# SCH_EEE3088F-Sphora_2025-04-07.net
KiCad netlist of a schematic drawn in EasyEDA
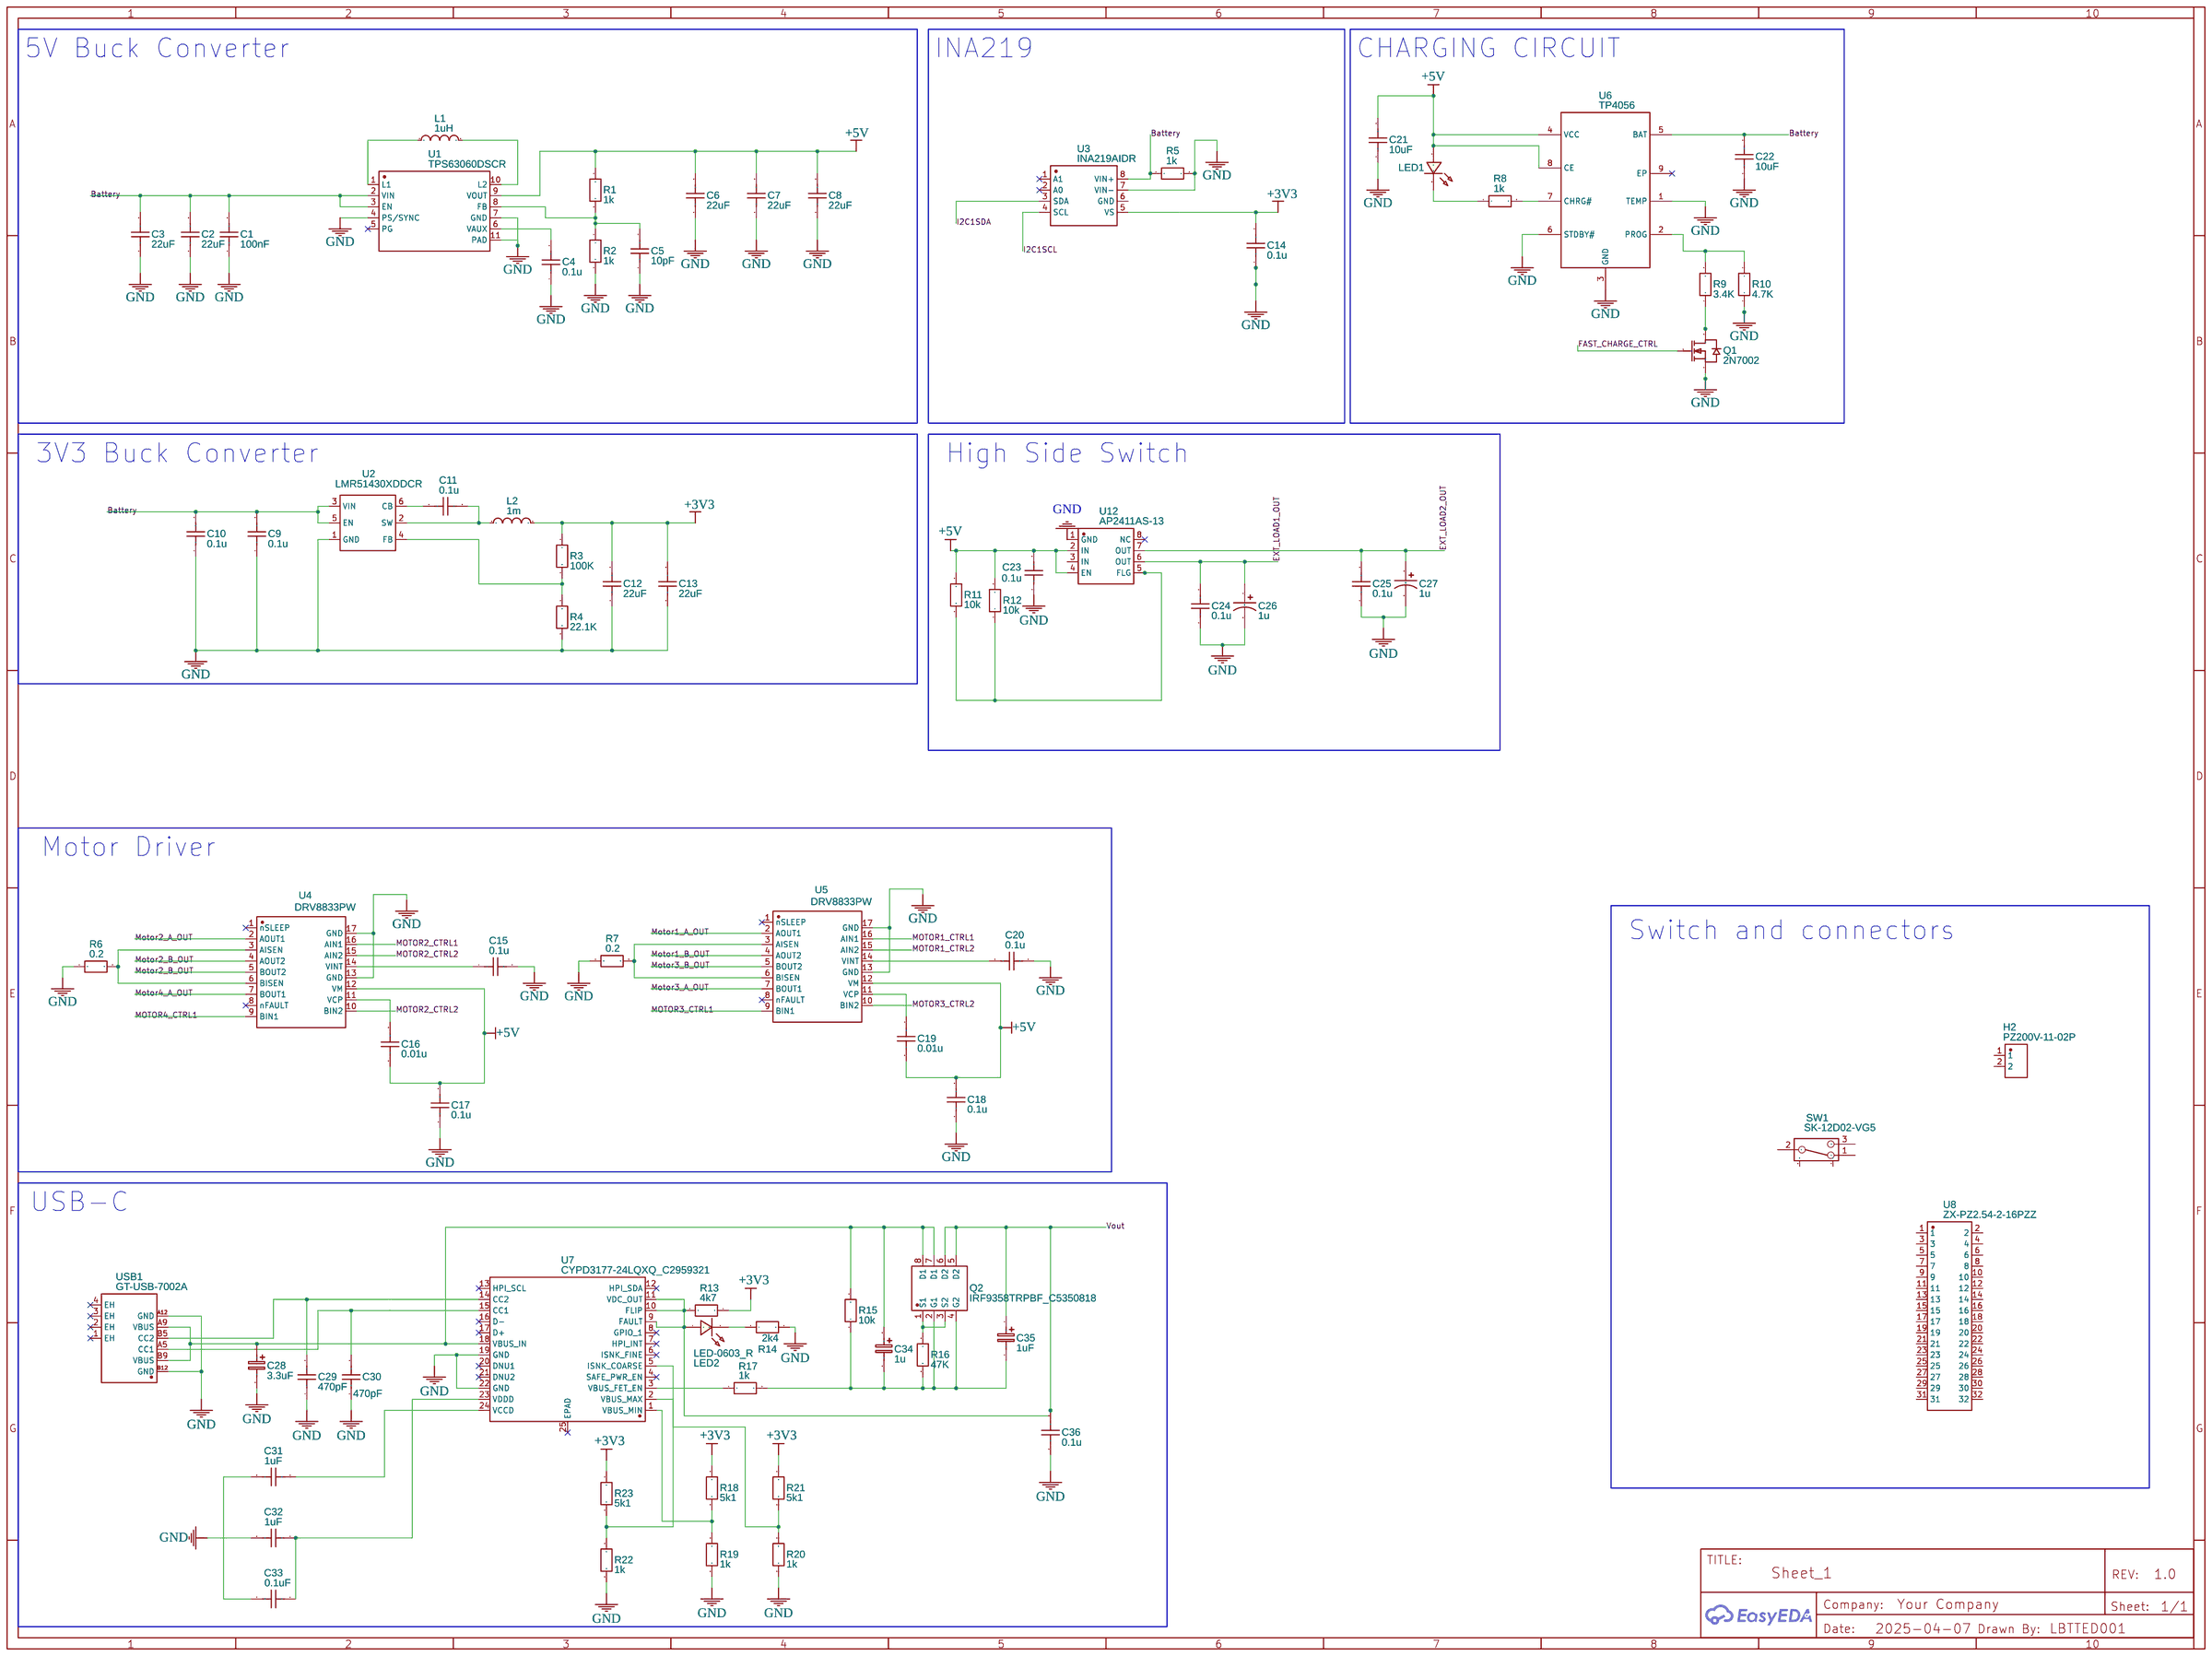
[diagram p0: schematic sheet]

(export (version "E")
  (design (tool "Eeschema 10.0.6"))
  (components
    (comp (ref "C1") (value "100nF") (libsource (lib "") (part "C_0402_US_1")))
    (comp (ref "C2") (value "22uF") (libsource (lib "") (part "C_0402_US_1")))
    (comp (ref "C3") (value "22uF") (libsource (lib "") (part "C_0402_US_1")))
    (comp (ref "C4") (value "0.1u") (libsource (lib "") (part "C_0402_US_1")))
    (comp (ref "C5") (value "10pF") (libsource (lib "") (part "C_0402_US_1")))
    (comp (ref "C6") (value "22uF") (libsource (lib "") (part "C_0402_US_1")))
    (comp (ref "C7") (value "22uF") (libsource (lib "") (part "C_0402_US_1")))
    (comp (ref "C8") (value "22uF") (libsource (lib "") (part "C_0402_US_1")))
    (comp (ref "C9") (value "0.1u") (libsource (lib "") (part "C_0402_US_1")))
    (comp (ref "C10") (value "0.1u") (libsource (lib "") (part "C_0402_US_1")))
    (comp (ref "C11") (value "0.1u") (libsource (lib "") (part "C_0402_US_2")))
    (comp (ref "C12") (value "22uF") (libsource (lib "") (part "C_0402_US_1")))
    (comp (ref "C13") (value "22uF") (libsource (lib "") (part "C_0402_US_1")))
    (comp (ref "C14") (value "0.1u") (libsource (lib "") (part "C_0402_US_3")))
    (comp (ref "C15") (value "0.1u") (libsource (lib "") (part "C_0402_US_2")))
    (comp (ref "C16") (value "0.01u") (libsource (lib "") (part "C_0402_US_1")))
    (comp (ref "C17") (value "0.1u") (libsource (lib "") (part "C_0402_US_1")))
    (comp (ref "C18") (value "0.1u") (libsource (lib "") (part "C_0402_US_1")))
    (comp (ref "C19") (value "0.01u") (libsource (lib "") (part "C_0402_US_1")))
    (comp (ref "C20") (value "0.1u") (libsource (lib "") (part "C_0402_US_2")))
    (comp (ref "C21") (value "10uF") (libsource (lib "") (part "C_0402_US_1")))
    (comp (ref "C22") (value "10uF") (libsource (lib "") (part "C_0402_US_1")))
    (comp (ref "C23") (value "0.1u") (libsource (lib "") (part "C_0402_US_1")))
    (comp (ref "C24") (value "0.1u") (libsource (lib "") (part "C_0402_US_1")))
    (comp (ref "C25") (value "0.1u") (libsource (lib "") (part "C_0402_US_1")))
    (comp (ref "C26") (value "1u") (libsource (lib "") (part "C_Tan_SMD_A_US")))
    (comp (ref "C27") (value "1u") (libsource (lib "") (part "C_Tan_SMD_A_US")))
    (comp (ref "C28") (value "3.3uF") (libsource (lib "") (part "C_Tan_SMD_A_EU_1")))
    (comp (ref "C29") (value "470pF") (libsource (lib "") (part "C_0402_US_1")))
    (comp (ref "C30") (value "470pF") (libsource (lib "") (part "C_0402_US_1")))
    (comp (ref "C31") (value "1uF") (libsource (lib "") (part "C_0402_US")))
    (comp (ref "C32") (value "1uF") (libsource (lib "") (part "C_0402_US")))
    (comp (ref "C33") (value "0.1uF") (libsource (lib "") (part "C_0402_US")))
    (comp (ref "C34") (value "1u") (libsource (lib "") (part "C_Tan_SMD_A_EU")))
    (comp (ref "C35") (value "1uF") (libsource (lib "") (part "C_Tan_SMD_A_EU")))
    (comp (ref "C36") (value "0.1u") (libsource (lib "") (part "C_0402_US_1")))
    (comp (ref "H2")
      (value "PZ200V-11-02P")
      (fields (field (name "Manufacturer") "XFCN(兴飞)"))
      (libsource (lib "") (part "PZ200V-11-02P"))
    )
    (comp (ref "L1") (value "1uH") (libsource (lib "") (part "L0603_US")))
    (comp (ref "L2") (value "1m") (libsource (lib "") (part "L0603_US")))
    (comp (ref "LED1")
      (value "LED-0603_R")
      (fields
        (field (name "Manufacturer Part") "19-217/R6C-AL1M2VY/3T")
        (field (name "Manufacturer") "EVERLIGHT(台湾亿光)")
      )
      (libsource (lib "") (part "LED-0603_R"))
    )
    (comp (ref "LED2")
      (value "LED-0603_R")
      (fields
        (field (name "Manufacturer Part") "19-217/R6C-AL1M2VY/3T")
        (field (name "Manufacturer") "EVERLIGHT(台湾亿光)")
      )
      (libsource (lib "") (part "LED-0603_R_1"))
    )
    (comp (ref "Q1")
      (value "2N7002")
      (fields (field (name "Manufacturer Part") "2N7002,215") (field (name "Manufacturer") "Nexperia"))
      (libsource (lib "") (part "2N7002"))
    )
    (comp (ref "Q2")
      (value "IRF9358TRPBF_C5350818")
      (fields
        (field (name "Manufacturer Part") "IRF9358TRPBF")
        (field (name "Manufacturer") "TECH PUBLIC(台舟)")
      )
      (libsource (lib "") (part "IRF9358TRPBF_C5350818"))
    )
    (comp (ref "R1") (value "1k") (libsource (lib "") (part "R_0402_EU")))
    (comp (ref "R2") (value "1k") (libsource (lib "") (part "R_0402_EU")))
    (comp (ref "R3") (value "100K") (libsource (lib "") (part "R_0402_EU_1")))
    (comp (ref "R4") (value "22.1K") (libsource (lib "") (part "R_0402_EU_1")))
    (comp (ref "R5") (value "1k") (libsource (lib "") (part "R_0402_EU_2")))
    (comp (ref "R6") (value "0.2") (libsource (lib "") (part "R_0402_EU_2")))
    (comp (ref "R7") (value "0.2") (libsource (lib "") (part "R_0402_EU_2")))
    (comp (ref "R8") (value "1k") (libsource (lib "") (part "R_0402_EU_2")))
    (comp (ref "R9") (value "3.4K") (libsource (lib "") (part "R_0402_EU_1")))
    (comp (ref "R10") (value "4.7K") (libsource (lib "") (part "R_0402_EU_1")))
    (comp (ref "R11") (value "10k") (libsource (lib "") (part "R_0402_EU_1")))
    (comp (ref "R12") (value "10k") (libsource (lib "") (part "R_0402_EU_1")))
    (comp (ref "R13") (value "4k7") (libsource (lib "") (part "R_0402_EU_2")))
    (comp (ref "R14") (value "2k4") (libsource (lib "") (part "R_0402_EU_2")))
    (comp (ref "R15") (value "10k") (libsource (lib "") (part "R_0402_EU_1")))
    (comp (ref "R16") (value "47K") (libsource (lib "") (part "R_0402_EU")))
    (comp (ref "R17") (value "1k") (libsource (lib "") (part "R_0402_EU_2")))
    (comp (ref "R18") (value "5k1") (libsource (lib "") (part "R_0402_EU")))
    (comp (ref "R19") (value "1k") (libsource (lib "") (part "R_0402_EU")))
    (comp (ref "R20") (value "1k") (libsource (lib "") (part "R_0402_EU")))
    (comp (ref "R21") (value "5k1") (libsource (lib "") (part "R_0402_EU")))
    (comp (ref "R22") (value "1k") (libsource (lib "") (part "R_0402_EU")))
    (comp (ref "R23") (value "5k1") (libsource (lib "") (part "R_0402_EU")))
    (comp (ref "SW1")
      (value "SK-12D02-VG5")
      (fields (field (name "Manufacturer") "Rectangular Connectors - Contacts"))
      (libsource (lib "") (part "SK-12D02-VG5"))
    )
    (comp (ref "U1")
      (value "TPS63060DSCR")
      (fields (field (name "Manufacturer") "TI(德州仪器)"))
      (libsource (lib "") (part "TPS63060DSCR"))
    )
    (comp (ref "U2")
      (value "LMR51430XDDCR")
      (fields (field (name "Manufacturer") "TI(德州仪器)"))
      (libsource (lib "") (part "LMR51430XDDCR"))
    )
    (comp (ref "U3")
      (value "INA219AIDR")
      (fields (field (name "Manufacturer") "TI(德州仪器)"))
      (libsource (lib "") (part "INA219AIDR"))
    )
    (comp (ref "U4") (value "DRV8833PW") (libsource (lib "") (part "DRV8833PW")))
    (comp (ref "U5") (value "DRV8833PW") (libsource (lib "") (part "DRV8833PW")))
    (comp (ref "U6")
      (value "TP4056")
      (fields
        (field (name "Manufacturer Part") "TP4056-42-ESOP8")
        (field (name "Manufacturer") "TOPPOWER(南京拓微)")
      )
      (libsource (lib "") (part "TP4056"))
    )
    (comp (ref "U7")
      (value "CYPD3177-24LQXQ_C2959321")
      (fields
        (field (name "Manufacturer Part") "CYPD3177-24LQXQ")
        (field (name "Manufacturer") "Infineon/CYPRESS(赛普拉斯)")
      )
      (libsource (lib "") (part "CYPD3177-24LQXQ_C2959321"))
    )
    (comp (ref "U8")
      (value "ZX-PZ2.54-2-16PZZ")
      (fields (field (name "Manufacturer") "Megastar(兆星)"))
      (libsource (lib "") (part "ZX-PZ2.54-2-16PZZ"))
    )
    (comp (ref "U12")
      (value "AP2411AS-13")
      (fields (field (name "Manufacturer") "DIODES(美台)"))
      (libsource (lib "") (part "AP2411AS-13"))
    )
    (comp (ref "USB1")
      (value "GT-USB-7002A")
      (fields (field (name "Manufacturer") "G-Switch(品赞)"))
      (libsource (lib "") (part "GT-USB-7002A"))
    )
  )
  (nets
    (net (code "1") (name "+3V3") (class "Default")
      (node (ref "C12") (pin "2") (pinfunction "2_2") (pintype "unspecified"))
      (node (ref "C13") (pin "2") (pinfunction "2_2") (pintype "unspecified"))
      (node (ref "C14") (pin "1") (pinfunction "1_1") (pintype "unspecified"))
      (node (ref "L2") (pin "2") (pinfunction "2_2") (pintype "unspecified"))
      (node (ref "R13") (pin "2") (pinfunction "2_2") (pintype "unspecified"))
      (node (ref "R18") (pin "1") (pinfunction "1_1") (pintype "unspecified"))
      (node (ref "R21") (pin "1") (pinfunction "1_1") (pintype "unspecified"))
      (node (ref "R23") (pin "1") (pinfunction "1_1") (pintype "unspecified"))
      (node (ref "R3") (pin "2") (pinfunction "2_2") (pintype "unspecified"))
      (node (ref "U3") (pin "5") (pinfunction "VS_5") (pintype "unspecified"))
    )
    (net (code "2") (name "+5V") (class "Default")
      (node (ref "C16") (pin "1") (pinfunction "1_1") (pintype "unspecified"))
      (node (ref "C17") (pin "2") (pinfunction "2_2") (pintype "unspecified"))
      (node (ref "C18") (pin "2") (pinfunction "2_2") (pintype "unspecified"))
      (node (ref "C19") (pin "1") (pinfunction "1_1") (pintype "unspecified"))
      (node (ref "C21") (pin "2") (pinfunction "2_2") (pintype "unspecified"))
      (node (ref "C23") (pin "2") (pinfunction "2_2") (pintype "unspecified"))
      (node (ref "C6") (pin "2") (pinfunction "2_2") (pintype "unspecified"))
      (node (ref "C7") (pin "2") (pinfunction "2_2") (pintype "unspecified"))
      (node (ref "C8") (pin "2") (pinfunction "2_2") (pintype "unspecified"))
      (node (ref "LED1") (pin "1") (pinfunction "1_1") (pintype "unspecified"))
      (node (ref "R1") (pin "1") (pinfunction "1_1") (pintype "unspecified"))
      (node (ref "R11") (pin "2") (pinfunction "2_2") (pintype "unspecified"))
      (node (ref "R12") (pin "2") (pinfunction "2_2") (pintype "unspecified"))
      (node (ref "U1") (pin "9") (pinfunction "VOUT_9") (pintype "unspecified"))
      (node (ref "U12") (pin "2") (pinfunction "IN_2") (pintype "unspecified"))
      (node (ref "U12") (pin "4") (pinfunction "EN_4") (pintype "unspecified"))
      (node (ref "U4") (pin "12") (pinfunction "VM_12") (pintype "unspecified"))
      (node (ref "U5") (pin "12") (pinfunction "VM_12") (pintype "unspecified"))
      (node (ref "U6") (pin "4") (pinfunction "VCC_4") (pintype "unspecified"))
      (node (ref "U6") (pin "8") (pinfunction "CE_8") (pintype "unspecified"))
    )
    (net (code "3") (name "/Battery") (class "Default")
      (node (ref "C1") (pin "2") (pinfunction "2_2") (pintype "unspecified"))
      (node (ref "C10") (pin "2") (pinfunction "2_2") (pintype "unspecified"))
      (node (ref "C2") (pin "2") (pinfunction "2_2") (pintype "unspecified"))
      (node (ref "C22") (pin "2") (pinfunction "2_2") (pintype "unspecified"))
      (node (ref "C3") (pin "2") (pinfunction "2_2") (pintype "unspecified"))
      (node (ref "C9") (pin "2") (pinfunction "2_2") (pintype "unspecified"))
      (node (ref "R5") (pin "1") (pinfunction "1_1") (pintype "unspecified"))
      (node (ref "U1") (pin "2") (pinfunction "VIN_2") (pintype "unspecified"))
      (node (ref "U1") (pin "3") (pinfunction "EN_3") (pintype "unspecified"))
      (node (ref "U2") (pin "3") (pinfunction "VIN_3") (pintype "unspecified"))
      (node (ref "U2") (pin "5") (pinfunction "EN_5") (pintype "unspecified"))
      (node (ref "U3") (pin "8") (pinfunction "VIN+_8") (pintype "unspecified"))
      (node (ref "U6") (pin "5") (pinfunction "BAT_5") (pintype "unspecified"))
    )
    (net (code "4") (name "/EXT_LOAD1_OUT") (class "Default")
      (node (ref "C24") (pin "2") (pinfunction "2_2") (pintype "unspecified"))
      (node (ref "C26") (pin "1") (pinfunction "1_1") (pintype "unspecified"))
      (node (ref "U12") (pin "6") (pinfunction "OUT_6") (pintype "unspecified"))
    )
    (net (code "5") (name "/EXT_LOAD2_OUT") (class "Default")
      (node (ref "C25") (pin "2") (pinfunction "2_2") (pintype "unspecified"))
      (node (ref "C27") (pin "1") (pinfunction "1_1") (pintype "unspecified"))
      (node (ref "U12") (pin "7") (pinfunction "OUT_7") (pintype "unspecified"))
    )
    (net (code "6") (name "/FAST_CHARGE_CTRL") (class "Default")
      (node (ref "Q1") (pin "1") (pinfunction "G_1") (pintype "unspecified"))
    )
    (net (code "7") (name "/I2C1SCL") (class "Default")
      (node (ref "U3") (pin "4") (pinfunction "SCL_4") (pintype "unspecified"))
    )
    (net (code "8") (name "/I2C1SDA") (class "Default")
      (node (ref "U3") (pin "3") (pinfunction "SDA_3") (pintype "unspecified"))
    )
    (net (code "9") (name "/MOTOR1_CTRL1") (class "Default")
      (node (ref "U5") (pin "16") (pinfunction "AIN1_16") (pintype "unspecified"))
    )
    (net (code "10") (name "/MOTOR1_CTRL2") (class "Default")
      (node (ref "U5") (pin "15") (pinfunction "AIN2_15") (pintype "unspecified"))
    )
    (net (code "11") (name "/MOTOR2_CTRL1") (class "Default")
      (node (ref "U4") (pin "16") (pinfunction "AIN1_16") (pintype "unspecified"))
    )
    (net (code "12") (name "/MOTOR2_CTRL2") (class "Default")
      (node (ref "U4") (pin "10") (pinfunction "BIN2_10") (pintype "unspecified"))
      (node (ref "U4") (pin "15") (pinfunction "AIN2_15") (pintype "unspecified"))
    )
    (net (code "13") (name "/MOTOR3_CTRL1") (class "Default")
      (node (ref "U5") (pin "9") (pinfunction "BIN1_9") (pintype "unspecified"))
    )
    (net (code "14") (name "/MOTOR3_CTRL2") (class "Default")
      (node (ref "U5") (pin "10") (pinfunction "BIN2_10") (pintype "unspecified"))
    )
    (net (code "15") (name "/MOTOR4_CTRL1") (class "Default")
      (node (ref "U4") (pin "9") (pinfunction "BIN1_9") (pintype "unspecified"))
    )
    (net (code "16") (name "/Motor1_A_OUT") (class "Default")
      (node (ref "U5") (pin "2") (pinfunction "AOUT1_2") (pintype "unspecified"))
    )
    (net (code "17") (name "/Motor1_B_OUT") (class "Default")
      (node (ref "U5") (pin "4") (pinfunction "AOUT2_4") (pintype "unspecified"))
    )
    (net (code "18") (name "/Motor2_A_OUT") (class "Default")
      (node (ref "U4") (pin "2") (pinfunction "AOUT1_2") (pintype "unspecified"))
    )
    (net (code "19") (name "/Motor2_B_OUT") (class "Default")
      (node (ref "U4") (pin "4") (pinfunction "AOUT2_4") (pintype "unspecified"))
      (node (ref "U4") (pin "5") (pinfunction "BOUT2_5") (pintype "unspecified"))
    )
    (net (code "20") (name "/Motor3_A_OUT") (class "Default")
      (node (ref "U5") (pin "7") (pinfunction "BOUT1_7") (pintype "unspecified"))
    )
    (net (code "21") (name "/Motor3_B_OUT") (class "Default")
      (node (ref "U5") (pin "5") (pinfunction "BOUT2_5") (pintype "unspecified"))
    )
    (net (code "22") (name "/Motor4_A_OUT") (class "Default")
      (node (ref "U4") (pin "7") (pinfunction "BOUT1_7") (pintype "unspecified"))
    )
    (net (code "23") (name "/Vout") (class "Default")
      (node (ref "C35") (pin "1") (pinfunction "1_1") (pintype "unspecified"))
      (node (ref "C36") (pin "2") (pinfunction "2_2") (pintype "unspecified"))
      (node (ref "LED2") (pin "1") (pinfunction "1_1") (pintype "unspecified"))
      (node (ref "Q2") (pin "5") (pinfunction "D2_5") (pintype "unspecified"))
      (node (ref "Q2") (pin "6") (pinfunction "D2_6") (pintype "unspecified"))
      (node (ref "R13") (pin "1") (pinfunction "1_1") (pintype "unspecified"))
      (node (ref "U7") (pin "10") (pinfunction "FLIP_10") (pintype "unspecified"))
      (node (ref "U7") (pin "11") (pinfunction "VDC_OUT_11") (pintype "unspecified"))
      (node (ref "U7") (pin "9") (pinfunction "FAULT_9") (pintype "unspecified"))
    )
    (net (code "24") (name "GND") (class "Default")
      (node (ref "C1") (pin "1") (pinfunction "1_1") (pintype "unspecified"))
      (node (ref "C10") (pin "1") (pinfunction "1_1") (pintype "unspecified"))
      (node (ref "C12") (pin "1") (pinfunction "1_1") (pintype "unspecified"))
      (node (ref "C13") (pin "1") (pinfunction "1_1") (pintype "unspecified"))
      (node (ref "C14") (pin "2") (pinfunction "2_2") (pintype "unspecified"))
      (node (ref "C15") (pin "2") (pinfunction "2_2") (pintype "unspecified"))
      (node (ref "C17") (pin "1") (pinfunction "1_1") (pintype "unspecified"))
      (node (ref "C18") (pin "1") (pinfunction "1_1") (pintype "unspecified"))
      (node (ref "C2") (pin "1") (pinfunction "1_1") (pintype "unspecified"))
      (node (ref "C20") (pin "2") (pinfunction "2_2") (pintype "unspecified"))
      (node (ref "C21") (pin "1") (pinfunction "1_1") (pintype "unspecified"))
      (node (ref "C22") (pin "1") (pinfunction "1_1") (pintype "unspecified"))
      (node (ref "C23") (pin "1") (pinfunction "1_1") (pintype "unspecified"))
      (node (ref "C24") (pin "1") (pinfunction "1_1") (pintype "unspecified"))
      (node (ref "C25") (pin "1") (pinfunction "1_1") (pintype "unspecified"))
      (node (ref "C26") (pin "2") (pinfunction "2_2") (pintype "unspecified"))
      (node (ref "C27") (pin "2") (pinfunction "2_2") (pintype "unspecified"))
      (node (ref "C28") (pin "2") (pinfunction "2_2") (pintype "unspecified"))
      (node (ref "C29") (pin "1") (pinfunction "1_1") (pintype "unspecified"))
      (node (ref "C3") (pin "1") (pinfunction "1_1") (pintype "unspecified"))
      (node (ref "C30") (pin "1") (pinfunction "1_1") (pintype "unspecified"))
      (node (ref "C32") (pin "2") (pinfunction "2_2") (pintype "unspecified"))
      (node (ref "C36") (pin "1") (pinfunction "1_1") (pintype "unspecified"))
      (node (ref "C4") (pin "1") (pinfunction "1_1") (pintype "unspecified"))
      (node (ref "C5") (pin "1") (pinfunction "1_1") (pintype "unspecified"))
      (node (ref "C6") (pin "1") (pinfunction "1_1") (pintype "unspecified"))
      (node (ref "C7") (pin "1") (pinfunction "1_1") (pintype "unspecified"))
      (node (ref "C8") (pin "1") (pinfunction "1_1") (pintype "unspecified"))
      (node (ref "C9") (pin "1") (pinfunction "1_1") (pintype "unspecified"))
      (node (ref "Q1") (pin "2") (pinfunction "S_2") (pintype "unspecified"))
      (node (ref "R10") (pin "1") (pinfunction "1_1") (pintype "unspecified"))
      (node (ref "R14") (pin "2") (pinfunction "2_2") (pintype "unspecified"))
      (node (ref "R19") (pin "2") (pinfunction "2_2") (pintype "unspecified"))
      (node (ref "R2") (pin "2") (pinfunction "2_2") (pintype "unspecified"))
      (node (ref "R20") (pin "2") (pinfunction "2_2") (pintype "unspecified"))
      (node (ref "R22") (pin "2") (pinfunction "2_2") (pintype "unspecified"))
      (node (ref "R4") (pin "1") (pinfunction "1_1") (pintype "unspecified"))
      (node (ref "R5") (pin "2") (pinfunction "2_2") (pintype "unspecified"))
      (node (ref "R6") (pin "1") (pinfunction "1_1") (pintype "unspecified"))
      (node (ref "R7") (pin "1") (pinfunction "1_1") (pintype "unspecified"))
      (node (ref "U1") (pin "11") (pinfunction "PAD_11") (pintype "unspecified"))
      (node (ref "U1") (pin "4") (pinfunction "PS/SYNC_4") (pintype "unspecified"))
      (node (ref "U1") (pin "7") (pinfunction "GND_7") (pintype "unspecified"))
      (node (ref "U12") (pin "1") (pinfunction "GND_1") (pintype "unspecified"))
      (node (ref "U2") (pin "1") (pinfunction "GND_1") (pintype "unspecified"))
      (node (ref "U3") (pin "7") (pinfunction "VIN-_7") (pintype "unspecified"))
      (node (ref "U4") (pin "13") (pinfunction "GND_13") (pintype "unspecified"))
      (node (ref "U4") (pin "17") (pinfunction "GND_17") (pintype "unspecified"))
      (node (ref "U5") (pin "13") (pinfunction "GND_13") (pintype "unspecified"))
      (node (ref "U5") (pin "17") (pinfunction "GND_17") (pintype "unspecified"))
      (node (ref "U6") (pin "1") (pinfunction "TEMP_1") (pintype "unspecified"))
      (node (ref "U6") (pin "3") (pinfunction "GND_3") (pintype "unspecified"))
      (node (ref "U6") (pin "6") (pinfunction "STDBY#_6") (pintype "unspecified"))
      (node (ref "U7") (pin "19") (pinfunction "GND_19") (pintype "unspecified"))
      (node (ref "U7") (pin "22") (pinfunction "GND_22") (pintype "unspecified"))
      (node (ref "USB1") (pin "A12") (pinfunction "GND_A12") (pintype "unspecified"))
      (node (ref "USB1") (pin "B12") (pinfunction "GND_B12") (pintype "unspecified"))
    )
    (net (code "25") (name "Net-(C31-Pad2)") (class "Default")
      (node (ref "C31") (pin "2") (pinfunction "2_2") (pintype "unspecified"))
      (node (ref "C33") (pin "2") (pinfunction "2_2") (pintype "unspecified"))
    )
    (net (code "26") (name "Net-(LED1-Pad2)") (class "Default")
      (node (ref "LED1") (pin "2") (pinfunction "2_2") (pintype "unspecified"))
      (node (ref "R8") (pin "1") (pinfunction "1_1") (pintype "unspecified"))
    )
    (net (code "27") (name "Net-(LED2-Pad2)") (class "Default")
      (node (ref "LED2") (pin "2") (pinfunction "2_2") (pintype "unspecified"))
      (node (ref "R14") (pin "1") (pinfunction "1_1") (pintype "unspecified"))
    )
    (net (code "28") (name "Net-(Q1-D)") (class "Default")
      (node (ref "Q1") (pin "3") (pinfunction "D_3") (pintype "unspecified"))
      (node (ref "R9") (pin "1") (pinfunction "1_1") (pintype "unspecified"))
    )
    (net (code "29") (name "Net-(Q2-G1)") (class "Default")
      (node (ref "C34") (pin "2") (pinfunction "2_2") (pintype "unspecified"))
      (node (ref "C35") (pin "2") (pinfunction "2_2") (pintype "unspecified"))
      (node (ref "Q2") (pin "2") (pinfunction "G1_2") (pintype "unspecified"))
      (node (ref "Q2") (pin "4") (pinfunction "G2_4") (pintype "unspecified"))
      (node (ref "R15") (pin "1") (pinfunction "1_1") (pintype "unspecified"))
      (node (ref "R16") (pin "2") (pinfunction "2_2") (pintype "unspecified"))
      (node (ref "R17") (pin "2") (pinfunction "2_2") (pintype "unspecified"))
    )
    (net (code "30") (name "Net-(Q2-S1)") (class "Default")
      (node (ref "Q2") (pin "1") (pinfunction "S1_1") (pintype "unspecified"))
      (node (ref "Q2") (pin "3") (pinfunction "S2_3") (pintype "unspecified"))
      (node (ref "R16") (pin "1") (pinfunction "1_1") (pintype "unspecified"))
    )
    (net (code "31") (name "Net-(U1-FB)") (class "Default")
      (node (ref "C5") (pin "2") (pinfunction "2_2") (pintype "unspecified"))
      (node (ref "R1") (pin "2") (pinfunction "2_2") (pintype "unspecified"))
      (node (ref "R2") (pin "1") (pinfunction "1_1") (pintype "unspecified"))
      (node (ref "U1") (pin "8") (pinfunction "FB_8") (pintype "unspecified"))
    )
    (net (code "32") (name "Net-(U1-L1)") (class "Default")
      (node (ref "L1") (pin "1") (pinfunction "1_1") (pintype "unspecified"))
      (node (ref "U1") (pin "1") (pinfunction "L1_1") (pintype "unspecified"))
    )
    (net (code "33") (name "Net-(U1-L2)") (class "Default")
      (node (ref "L1") (pin "2") (pinfunction "2_2") (pintype "unspecified"))
      (node (ref "U1") (pin "10") (pinfunction "L2_10") (pintype "unspecified"))
    )
    (net (code "34") (name "Net-(U1-VAUX)") (class "Default")
      (node (ref "C4") (pin "2") (pinfunction "2_2") (pintype "unspecified"))
      (node (ref "U1") (pin "6") (pinfunction "VAUX_6") (pintype "unspecified"))
    )
    (net (code "35") (name "Net-(U2-CB)") (class "Default")
      (node (ref "C11") (pin "1") (pinfunction "1_1") (pintype "unspecified"))
      (node (ref "U2") (pin "6") (pinfunction "CB_6") (pintype "unspecified"))
    )
    (net (code "36") (name "Net-(U2-FB)") (class "Default")
      (node (ref "R3") (pin "1") (pinfunction "1_1") (pintype "unspecified"))
      (node (ref "R4") (pin "2") (pinfunction "2_2") (pintype "unspecified"))
      (node (ref "U2") (pin "4") (pinfunction "FB_4") (pintype "unspecified"))
    )
    (net (code "37") (name "Net-(U2-SW)") (class "Default")
      (node (ref "C11") (pin "2") (pinfunction "2_2") (pintype "unspecified"))
      (node (ref "L2") (pin "1") (pinfunction "1_1") (pintype "unspecified"))
      (node (ref "U2") (pin "2") (pinfunction "SW_2") (pintype "unspecified"))
    )
    (net (code "38") (name "Net-(U4-AISEN)") (class "Default")
      (node (ref "R6") (pin "2") (pinfunction "2_2") (pintype "unspecified"))
      (node (ref "U4") (pin "3") (pinfunction "AISEN_3") (pintype "unspecified"))
      (node (ref "U4") (pin "6") (pinfunction "BISEN_6") (pintype "unspecified"))
    )
    (net (code "39") (name "Net-(U4-VCP)") (class "Default")
      (node (ref "C16") (pin "2") (pinfunction "2_2") (pintype "unspecified"))
      (node (ref "U4") (pin "11") (pinfunction "VCP_11") (pintype "unspecified"))
    )
    (net (code "40") (name "Net-(U4-VINT)") (class "Default")
      (node (ref "C15") (pin "1") (pinfunction "1_1") (pintype "unspecified"))
      (node (ref "U4") (pin "14") (pinfunction "VINT_14") (pintype "unspecified"))
    )
    (net (code "41") (name "Net-(U5-AISEN)") (class "Default")
      (node (ref "R7") (pin "2") (pinfunction "2_2") (pintype "unspecified"))
      (node (ref "U5") (pin "3") (pinfunction "AISEN_3") (pintype "unspecified"))
      (node (ref "U5") (pin "6") (pinfunction "BISEN_6") (pintype "unspecified"))
    )
    (net (code "42") (name "Net-(U5-VCP)") (class "Default")
      (node (ref "C19") (pin "2") (pinfunction "2_2") (pintype "unspecified"))
      (node (ref "U5") (pin "11") (pinfunction "VCP_11") (pintype "unspecified"))
    )
    (net (code "43") (name "Net-(U5-VINT)") (class "Default")
      (node (ref "C20") (pin "1") (pinfunction "1_1") (pintype "unspecified"))
      (node (ref "U5") (pin "14") (pinfunction "VINT_14") (pintype "unspecified"))
    )
    (net (code "44") (name "Net-(U6-CHRG#)") (class "Default")
      (node (ref "R8") (pin "2") (pinfunction "2_2") (pintype "unspecified"))
      (node (ref "U6") (pin "7") (pinfunction "CHRG#_7") (pintype "unspecified"))
    )
    (net (code "45") (name "Net-(U6-PROG)") (class "Default")
      (node (ref "R10") (pin "2") (pinfunction "2_2") (pintype "unspecified"))
      (node (ref "R9") (pin "2") (pinfunction "2_2") (pintype "unspecified"))
      (node (ref "U6") (pin "2") (pinfunction "PROG_2") (pintype "unspecified"))
    )
    (net (code "46") (name "Net-(U7-CC1)") (class "Default")
      (node (ref "C30") (pin "2") (pinfunction "2_2") (pintype "unspecified"))
      (node (ref "U7") (pin "15") (pinfunction "CC1_15") (pintype "unspecified"))
      (node (ref "USB1") (pin "A5") (pinfunction "CC1_A5") (pintype "unspecified"))
    )
    (net (code "47") (name "Net-(U7-CC2)") (class "Default")
      (node (ref "C29") (pin "2") (pinfunction "2_2") (pintype "unspecified"))
      (node (ref "U7") (pin "14") (pinfunction "CC2_14") (pintype "unspecified"))
      (node (ref "USB1") (pin "B5") (pinfunction "CC2_B5") (pintype "unspecified"))
    )
    (net (code "48") (name "Net-(U7-ISNK_COARSE)") (class "Default")
      (node (ref "R22") (pin "1") (pinfunction "1_1") (pintype "unspecified"))
      (node (ref "R23") (pin "2") (pinfunction "2_2") (pintype "unspecified"))
      (node (ref "U7") (pin "5") (pinfunction "ISNK_COARSE_5") (pintype "unspecified"))
    )
    (net (code "49") (name "Net-(U7-VBUS_FET_EN)") (class "Default")
      (node (ref "R17") (pin "1") (pinfunction "1_1") (pintype "unspecified"))
      (node (ref "U7") (pin "3") (pinfunction "VBUS_FET_EN_3") (pintype "unspecified"))
    )
    (net (code "50") (name "Net-(U7-VBUS_IN)") (class "Default")
      (node (ref "C28") (pin "1") (pinfunction "1_1") (pintype "unspecified"))
      (node (ref "C34") (pin "1") (pinfunction "1_1") (pintype "unspecified"))
      (node (ref "Q2") (pin "7") (pinfunction "D1_7") (pintype "unspecified"))
      (node (ref "Q2") (pin "8") (pinfunction "D1_8") (pintype "unspecified"))
      (node (ref "R15") (pin "2") (pinfunction "2_2") (pintype "unspecified"))
      (node (ref "U7") (pin "18") (pinfunction "VBUS_IN_18") (pintype "unspecified"))
      (node (ref "USB1") (pin "A9") (pinfunction "VBUS_A9") (pintype "unspecified"))
      (node (ref "USB1") (pin "B9") (pinfunction "VBUS_B9") (pintype "unspecified"))
    )
    (net (code "51") (name "Net-(U7-VBUS_MAX)") (class "Default")
      (node (ref "R20") (pin "1") (pinfunction "1_1") (pintype "unspecified"))
      (node (ref "R21") (pin "2") (pinfunction "2_2") (pintype "unspecified"))
      (node (ref "U7") (pin "2") (pinfunction "VBUS_MAX_2") (pintype "unspecified"))
    )
    (net (code "52") (name "Net-(U7-VBUS_MIN)") (class "Default")
      (node (ref "R18") (pin "2") (pinfunction "2_2") (pintype "unspecified"))
      (node (ref "R19") (pin "1") (pinfunction "1_1") (pintype "unspecified"))
      (node (ref "U7") (pin "1") (pinfunction "VBUS_MIN_1") (pintype "unspecified"))
    )
    (net (code "53") (name "Net-(U7-VCCD)") (class "Default")
      (node (ref "C31") (pin "1") (pinfunction "1_1") (pintype "unspecified"))
      (node (ref "U7") (pin "24") (pinfunction "VCCD_24") (pintype "unspecified"))
    )
    (net (code "54") (name "Net-(U7-VDDD)") (class "Default")
      (node (ref "C32") (pin "1") (pinfunction "1_1") (pintype "unspecified"))
      (node (ref "C33") (pin "1") (pinfunction "1_1") (pintype "unspecified"))
      (node (ref "U7") (pin "23") (pinfunction "VDDD_23") (pintype "unspecified"))
    )
    (net (code "55") (name "Net-(U12-FLG)") (class "Default")
      (node (ref "R11") (pin "1") (pinfunction "1_1") (pintype "unspecified"))
      (node (ref "R12") (pin "1") (pinfunction "1_1") (pintype "unspecified"))
      (node (ref "U12") (pin "5") (pinfunction "FLG_5") (pintype "unspecified"))
    )
    (net (code "56") (name "unconnected-(H2-Pad1)") (class "Default")
      (node (ref "H2") (pin "1") (pinfunction "1_1") (pintype "unspecified"))
    )
    (net (code "57") (name "unconnected-(H2-Pad2)") (class "Default")
      (node (ref "H2") (pin "2") (pinfunction "2_2") (pintype "unspecified"))
    )
    (net (code "58") (name "unconnected-(SW1-Pad1)") (class "Default")
      (node (ref "SW1") (pin "1") (pinfunction "1_1") (pintype "unspecified"))
    )
    (net (code "59") (name "unconnected-(SW1-Pad2)") (class "Default")
      (node (ref "SW1") (pin "2") (pinfunction "2_2") (pintype "unspecified"))
    )
    (net (code "60") (name "unconnected-(SW1-Pad3)") (class "Default")
      (node (ref "SW1") (pin "3") (pinfunction "3_3") (pintype "unspecified"))
    )
    (net (code "61") (name "unconnected-(SW1-Pad4)") (class "Default")
      (node (ref "SW1") (pin "4") (pinfunction "4_4") (pintype "unspecified"))
    )
    (net (code "62") (name "unconnected-(SW1-Pad5)") (class "Default")
      (node (ref "SW1") (pin "5") (pinfunction "5_5") (pintype "unspecified"))
    )
    (net (code "63") (name "unconnected-(U1-PG-Pad5)") (class "Default")
      (node (ref "U1") (pin "5") (pinfunction "PG_5") (pintype "unspecified+no_connect"))
    )
    (net (code "64") (name "unconnected-(U3-A0-Pad2)") (class "Default")
      (node (ref "U3") (pin "2") (pinfunction "A0_2") (pintype "unspecified+no_connect"))
    )
    (net (code "65") (name "unconnected-(U3-A1-Pad1)") (class "Default")
      (node (ref "U3") (pin "1") (pinfunction "A1_1") (pintype "unspecified+no_connect"))
    )
    (net (code "66") (name "unconnected-(U3-GND-Pad6)") (class "Default")
      (node (ref "U3") (pin "6") (pinfunction "GND_6") (pintype "unspecified"))
    )
    (net (code "67") (name "unconnected-(U4-nFAULT-Pad8)") (class "Default")
      (node (ref "U4") (pin "8") (pinfunction "nFAULT_8") (pintype "unspecified+no_connect"))
    )
    (net (code "68") (name "unconnected-(U4-nSLEEP-Pad1)") (class "Default")
      (node (ref "U4") (pin "1") (pinfunction "nSLEEP_1") (pintype "unspecified+no_connect"))
    )
    (net (code "69") (name "unconnected-(U5-nFAULT-Pad8)") (class "Default")
      (node (ref "U5") (pin "8") (pinfunction "nFAULT_8") (pintype "unspecified+no_connect"))
    )
    (net (code "70") (name "unconnected-(U5-nSLEEP-Pad1)") (class "Default")
      (node (ref "U5") (pin "1") (pinfunction "nSLEEP_1") (pintype "unspecified+no_connect"))
    )
    (net (code "71") (name "unconnected-(U6-EP-Pad9)") (class "Default")
      (node (ref "U6") (pin "9") (pinfunction "EP_9") (pintype "unspecified+no_connect"))
    )
    (net (code "72") (name "unconnected-(U7-D+-Pad17)") (class "Default")
      (node (ref "U7") (pin "17") (pinfunction "D+_17") (pintype "unspecified+no_connect"))
    )
    (net (code "73") (name "unconnected-(U7-D--Pad16)") (class "Default")
      (node (ref "U7") (pin "16") (pinfunction "D-_16") (pintype "unspecified+no_connect"))
    )
    (net (code "74") (name "unconnected-(U7-DNU1-Pad20)") (class "Default")
      (node (ref "U7") (pin "20") (pinfunction "DNU1_20") (pintype "unspecified+no_connect"))
    )
    (net (code "75") (name "unconnected-(U7-DNU2-Pad21)") (class "Default")
      (node (ref "U7") (pin "21") (pinfunction "DNU2_21") (pintype "unspecified+no_connect"))
    )
    (net (code "76") (name "unconnected-(U7-EPAD-Pad25)") (class "Default")
      (node (ref "U7") (pin "25") (pinfunction "EPAD_25") (pintype "unspecified+no_connect"))
    )
    (net (code "77") (name "unconnected-(U7-GPIO_1-Pad8)") (class "Default")
      (node (ref "U7") (pin "8") (pinfunction "GPIO_1_8") (pintype "unspecified+no_connect"))
    )
    (net (code "78") (name "unconnected-(U7-HPI_INT-Pad7)") (class "Default")
      (node (ref "U7") (pin "7") (pinfunction "HPI_INT_7") (pintype "unspecified+no_connect"))
    )
    (net (code "79") (name "unconnected-(U7-HPI_SCL-Pad13)") (class "Default")
      (node (ref "U7") (pin "13") (pinfunction "HPI_SCL_13") (pintype "unspecified+no_connect"))
    )
    (net (code "80") (name "unconnected-(U7-HPI_SDA-Pad12)") (class "Default")
      (node (ref "U7") (pin "12") (pinfunction "HPI_SDA_12") (pintype "unspecified+no_connect"))
    )
    (net (code "81") (name "unconnected-(U7-ISNK_FINE-Pad6)") (class "Default")
      (node (ref "U7") (pin "6") (pinfunction "ISNK_FINE_6") (pintype "unspecified+no_connect"))
    )
    (net (code "82") (name "unconnected-(U7-SAFE_PWR_EN-Pad4)") (class "Default")
      (node (ref "U7") (pin "4") (pinfunction "SAFE_PWR_EN_4") (pintype "unspecified+no_connect"))
    )
    (net (code "83") (name "unconnected-(U8-Pad1)") (class "Default")
      (node (ref "U8") (pin "1") (pinfunction "1_1") (pintype "unspecified"))
    )
    (net (code "84") (name "unconnected-(U8-Pad2)") (class "Default")
      (node (ref "U8") (pin "2") (pinfunction "2_2") (pintype "unspecified"))
    )
    (net (code "85") (name "unconnected-(U8-Pad3)") (class "Default")
      (node (ref "U8") (pin "3") (pinfunction "3_3") (pintype "unspecified"))
    )
    (net (code "86") (name "unconnected-(U8-Pad4)") (class "Default")
      (node (ref "U8") (pin "4") (pinfunction "4_4") (pintype "unspecified"))
    )
    (net (code "87") (name "unconnected-(U8-Pad5)") (class "Default")
      (node (ref "U8") (pin "5") (pinfunction "5_5") (pintype "unspecified"))
    )
    (net (code "88") (name "unconnected-(U8-Pad6)") (class "Default")
      (node (ref "U8") (pin "6") (pinfunction "6_6") (pintype "unspecified"))
    )
    (net (code "89") (name "unconnected-(U8-Pad7)") (class "Default")
      (node (ref "U8") (pin "7") (pinfunction "7_7") (pintype "unspecified"))
    )
    (net (code "90") (name "unconnected-(U8-Pad8)") (class "Default")
      (node (ref "U8") (pin "8") (pinfunction "8_8") (pintype "unspecified"))
    )
    (net (code "91") (name "unconnected-(U8-Pad9)") (class "Default")
      (node (ref "U8") (pin "9") (pinfunction "9_9") (pintype "unspecified"))
    )
    (net (code "92") (name "unconnected-(U8-Pad10)") (class "Default")
      (node (ref "U8") (pin "10") (pinfunction "10_10") (pintype "unspecified"))
    )
    (net (code "93") (name "unconnected-(U8-Pad11)") (class "Default")
      (node (ref "U8") (pin "11") (pinfunction "11_11") (pintype "unspecified"))
    )
    (net (code "94") (name "unconnected-(U8-Pad12)") (class "Default")
      (node (ref "U8") (pin "12") (pinfunction "12_12") (pintype "unspecified"))
    )
    (net (code "95") (name "unconnected-(U8-Pad13)") (class "Default")
      (node (ref "U8") (pin "13") (pinfunction "13_13") (pintype "unspecified"))
    )
    (net (code "96") (name "unconnected-(U8-Pad14)") (class "Default")
      (node (ref "U8") (pin "14") (pinfunction "14_14") (pintype "unspecified"))
    )
    (net (code "97") (name "unconnected-(U8-Pad15)") (class "Default")
      (node (ref "U8") (pin "15") (pinfunction "15_15") (pintype "unspecified"))
    )
    (net (code "98") (name "unconnected-(U8-Pad16)") (class "Default")
      (node (ref "U8") (pin "16") (pinfunction "16_16") (pintype "unspecified"))
    )
    (net (code "99") (name "unconnected-(U8-Pad17)") (class "Default")
      (node (ref "U8") (pin "17") (pinfunction "17_17") (pintype "unspecified"))
    )
    (net (code "100") (name "unconnected-(U8-Pad18)") (class "Default")
      (node (ref "U8") (pin "18") (pinfunction "18_18") (pintype "unspecified"))
    )
    (net (code "101") (name "unconnected-(U8-Pad19)") (class "Default")
      (node (ref "U8") (pin "19") (pinfunction "19_19") (pintype "unspecified"))
    )
    (net (code "102") (name "unconnected-(U8-Pad20)") (class "Default")
      (node (ref "U8") (pin "20") (pinfunction "20_20") (pintype "unspecified"))
    )
    (net (code "103") (name "unconnected-(U8-Pad21)") (class "Default")
      (node (ref "U8") (pin "21") (pinfunction "21_21") (pintype "unspecified"))
    )
    (net (code "104") (name "unconnected-(U8-Pad22)") (class "Default")
      (node (ref "U8") (pin "22") (pinfunction "22_22") (pintype "unspecified"))
    )
    (net (code "105") (name "unconnected-(U8-Pad23)") (class "Default")
      (node (ref "U8") (pin "23") (pinfunction "23_23") (pintype "unspecified"))
    )
    (net (code "106") (name "unconnected-(U8-Pad24)") (class "Default")
      (node (ref "U8") (pin "24") (pinfunction "24_24") (pintype "unspecified"))
    )
    (net (code "107") (name "unconnected-(U8-Pad25)") (class "Default")
      (node (ref "U8") (pin "25") (pinfunction "25_25") (pintype "unspecified"))
    )
    (net (code "108") (name "unconnected-(U8-Pad26)") (class "Default")
      (node (ref "U8") (pin "26") (pinfunction "26_26") (pintype "unspecified"))
    )
    (net (code "109") (name "unconnected-(U8-Pad27)") (class "Default")
      (node (ref "U8") (pin "27") (pinfunction "27_27") (pintype "unspecified"))
    )
    (net (code "110") (name "unconnected-(U8-Pad28)") (class "Default")
      (node (ref "U8") (pin "28") (pinfunction "28_28") (pintype "unspecified"))
    )
    (net (code "111") (name "unconnected-(U8-Pad29)") (class "Default")
      (node (ref "U8") (pin "29") (pinfunction "29_29") (pintype "unspecified"))
    )
    (net (code "112") (name "unconnected-(U8-Pad30)") (class "Default")
      (node (ref "U8") (pin "30") (pinfunction "30_30") (pintype "unspecified"))
    )
    (net (code "113") (name "unconnected-(U8-Pad31)") (class "Default")
      (node (ref "U8") (pin "31") (pinfunction "31_31") (pintype "unspecified"))
    )
    (net (code "114") (name "unconnected-(U8-Pad32)") (class "Default")
      (node (ref "U8") (pin "32") (pinfunction "32_32") (pintype "unspecified"))
    )
    (net (code "115") (name "unconnected-(U12-IN-Pad3)") (class "Default")
      (node (ref "U12") (pin "3") (pinfunction "IN_3") (pintype "unspecified"))
    )
    (net (code "116") (name "unconnected-(U12-NC-Pad8)") (class "Default")
      (node (ref "U12") (pin "8") (pinfunction "NC_8") (pintype "unspecified+no_connect"))
    )
    (net (code "117") (name "unconnected-(USB1-EH-Pad1)") (class "Default")
      (node (ref "USB1") (pin "1") (pinfunction "EH_1") (pintype "unspecified+no_connect"))
    )
    (net (code "118") (name "unconnected-(USB1-EH-Pad2)") (class "Default")
      (node (ref "USB1") (pin "2") (pinfunction "EH_2") (pintype "unspecified+no_connect"))
    )
    (net (code "119") (name "unconnected-(USB1-EH-Pad3)") (class "Default")
      (node (ref "USB1") (pin "3") (pinfunction "EH_3") (pintype "unspecified+no_connect"))
    )
    (net (code "120") (name "unconnected-(USB1-EH-Pad4)") (class "Default")
      (node (ref "USB1") (pin "4") (pinfunction "EH_4") (pintype "unspecified+no_connect"))
    )
  )
)
